# preamp.net
KiCad netlist of a schematic drawn in Altium Designer
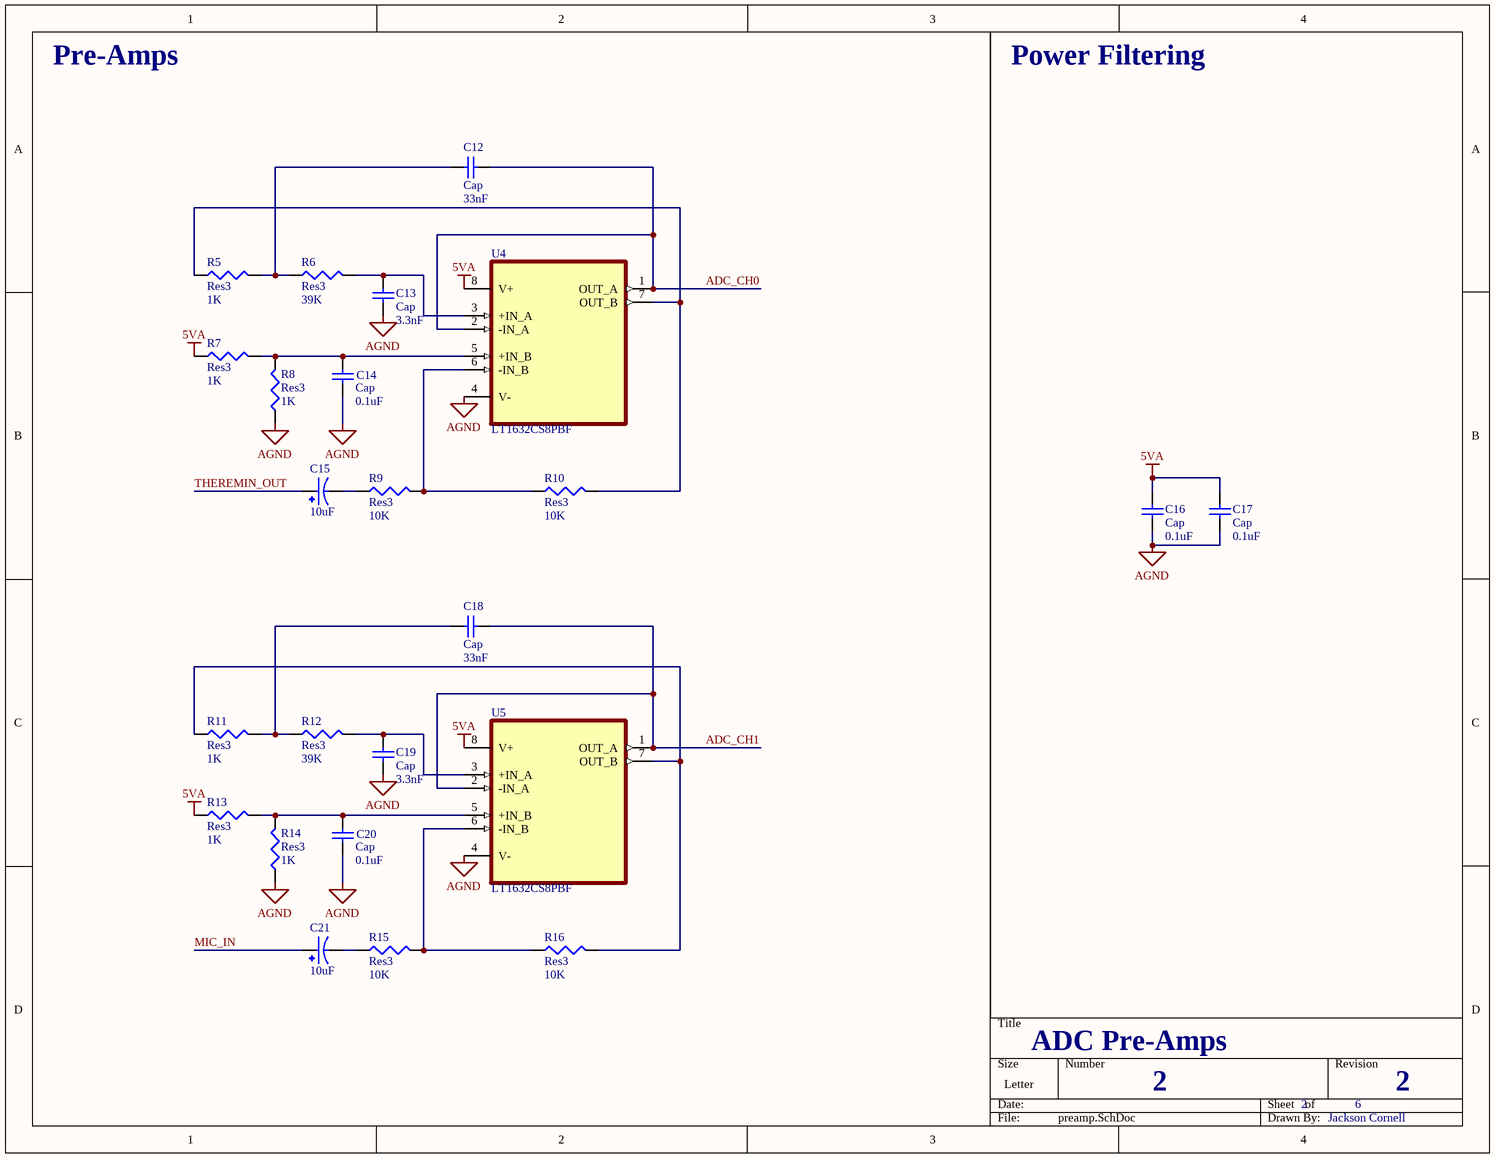
[diagram p0: preamp.SchDoc]

(export (version "E")
  (design (tool "Eeschema 10.0.6"))
  (components
    (comp (ref "C12")
      (value "Cap")
      (footprint "CAPC0805")
      (description "Capacitor")
      (fields (field (name "ALTIUM_VALUE") "33nF") (field (name "PUBLISHER") "Altium Limited"))
      (libsource (lib "Miscellaneous Devices") (part "Cap"))
    )
    (comp (ref "C13")
      (value "Cap")
      (footprint "CAPC0805")
      (description "Capacitor")
      (fields (field (name "ALTIUM_VALUE") "3.3nF") (field (name "PUBLISHER") "Altium Limited"))
      (libsource (lib "Miscellaneous Devices") (part "Cap"))
    )
    (comp (ref "C14")
      (value "Cap")
      (footprint "CAPC0805")
      (description "Capacitor")
      (fields (field (name "ALTIUM_VALUE") "0.1uF") (field (name "PUBLISHER") "Altium Limited"))
      (libsource (lib "Miscellaneous Devices") (part "Cap"))
    )
    (comp (ref "C15")
      (value "10uF")
      (footprint "CAPPRD200W50D500H1250")
      (description "Aluminum Electrolytic Capacitors, 220uF, 6.3V, -40 to 105C")
      (fields (field (name "MF") "Panasonic") (field (name "MP") "EEUFS0J221B"))
      (libsource (lib "EEUFS0J221B") (part "EEUFS0J221B"))
    )
    (comp (ref "C16")
      (value "Cap")
      (footprint "CAPC0805")
      (description "Capacitor")
      (fields (field (name "ALTIUM_VALUE") "0.1uF") (field (name "PUBLISHER") "Altium Limited"))
      (libsource (lib "Miscellaneous Devices") (part "Cap"))
    )
    (comp (ref "C17")
      (value "Cap")
      (footprint "CAPC0805")
      (description "Capacitor")
      (fields (field (name "ALTIUM_VALUE") "0.1uF") (field (name "PUBLISHER") "Altium Limited"))
      (libsource (lib "Miscellaneous Devices") (part "Cap"))
    )
    (comp (ref "C18")
      (value "Cap")
      (footprint "CAPC0805")
      (description "Capacitor")
      (fields (field (name "ALTIUM_VALUE") "33nF") (field (name "PUBLISHER") "Altium Limited"))
      (libsource (lib "Miscellaneous Devices") (part "Cap"))
    )
    (comp (ref "C19")
      (value "Cap")
      (footprint "CAPC0805")
      (description "Capacitor")
      (fields (field (name "ALTIUM_VALUE") "3.3nF") (field (name "PUBLISHER") "Altium Limited"))
      (libsource (lib "Miscellaneous Devices") (part "Cap"))
    )
    (comp (ref "C20")
      (value "Cap")
      (footprint "CAPC0805")
      (description "Capacitor")
      (fields (field (name "ALTIUM_VALUE") "0.1uF") (field (name "PUBLISHER") "Altium Limited"))
      (libsource (lib "Miscellaneous Devices") (part "Cap"))
    )
    (comp (ref "C21")
      (value "10uF")
      (footprint "CAPPRD200W50D500H1250")
      (description "Aluminum Electrolytic Capacitors, 220uF, 6.3V, -40 to 105C")
      (fields (field (name "MF") "Panasonic") (field (name "MP") "EEUFS0J221B"))
      (libsource (lib "EEUFS0J221B") (part "EEUFS0J221B"))
    )
    (comp (ref "R5")
      (value "Res3")
      (footprint "RES0805")
      (description "Resistor")
      (fields (field (name "ALTIUM_VALUE") "1K") (field (name "PUBLISHER") "Altium Limited"))
      (libsource (lib "Miscellaneous Devices") (part "Res3"))
    )
    (comp (ref "R6")
      (value "Res3")
      (footprint "RES0805")
      (description "Resistor")
      (fields (field (name "ALTIUM_VALUE") "39K") (field (name "PUBLISHER") "Altium Limited"))
      (libsource (lib "Miscellaneous Devices") (part "Res3"))
    )
    (comp (ref "R7")
      (value "Res3")
      (footprint "RES0805")
      (description "Resistor")
      (fields (field (name "ALTIUM_VALUE") "1K") (field (name "PUBLISHER") "Altium Limited"))
      (libsource (lib "Miscellaneous Devices") (part "Res3"))
    )
    (comp (ref "R8")
      (value "Res3")
      (footprint "RES0805")
      (description "Resistor")
      (fields (field (name "ALTIUM_VALUE") "1K") (field (name "PUBLISHER") "Altium Limited"))
      (libsource (lib "Miscellaneous Devices") (part "Res3"))
    )
    (comp (ref "R9")
      (value "Res3")
      (footprint "RES0805")
      (description "Resistor")
      (fields (field (name "ALTIUM_VALUE") "10K") (field (name "PUBLISHER") "Altium Limited"))
      (libsource (lib "Miscellaneous Devices") (part "Res3"))
    )
    (comp (ref "R10")
      (value "Res3")
      (footprint "RES0805")
      (description "Resistor")
      (fields (field (name "ALTIUM_VALUE") "10K") (field (name "PUBLISHER") "Altium Limited"))
      (libsource (lib "Miscellaneous Devices") (part "Res3"))
    )
    (comp (ref "R11")
      (value "Res3")
      (footprint "RES0805")
      (description "Resistor")
      (fields (field (name "ALTIUM_VALUE") "1K") (field (name "PUBLISHER") "Altium Limited"))
      (libsource (lib "Miscellaneous Devices") (part "Res3"))
    )
    (comp (ref "R12")
      (value "Res3")
      (footprint "RES0805")
      (description "Resistor")
      (fields (field (name "ALTIUM_VALUE") "39K") (field (name "PUBLISHER") "Altium Limited"))
      (libsource (lib "Miscellaneous Devices") (part "Res3"))
    )
    (comp (ref "R13")
      (value "Res3")
      (footprint "RES0805")
      (description "Resistor")
      (fields (field (name "ALTIUM_VALUE") "1K") (field (name "PUBLISHER") "Altium Limited"))
      (libsource (lib "Miscellaneous Devices") (part "Res3"))
    )
    (comp (ref "R14")
      (value "Res3")
      (footprint "RES0805")
      (description "Resistor")
      (fields (field (name "ALTIUM_VALUE") "1K") (field (name "PUBLISHER") "Altium Limited"))
      (libsource (lib "Miscellaneous Devices") (part "Res3"))
    )
    (comp (ref "R15")
      (value "Res3")
      (footprint "RES0805")
      (description "Resistor")
      (fields (field (name "ALTIUM_VALUE") "10K") (field (name "PUBLISHER") "Altium Limited"))
      (libsource (lib "Miscellaneous Devices") (part "Res3"))
    )
    (comp (ref "R16")
      (value "Res3")
      (footprint "RES0805")
      (description "Resistor")
      (fields (field (name "ALTIUM_VALUE") "10K") (field (name "PUBLISHER") "Altium Limited"))
      (libsource (lib "Miscellaneous Devices") (part "Res3"))
    )
    (comp (ref "U4")
      (value "LT1632CS8PBF")
      (footprint "SO-8_S")
      (description "45MHz, 45V/ms, Dual/Quad Rail-to-Rail Input and Output  Precision Op Amps")
      (libsource (lib "LT1632CS8PBF") (part "LT1632CS8PBF"))
    )
    (comp (ref "U5")
      (value "LT1632CS8PBF")
      (footprint "SO-8_S")
      (description "45MHz, 45V/ms, Dual/Quad Rail-to-Rail Input and Output  Precision Op Amps")
      (libsource (lib "LT1632CS8PBF") (part "LT1632CS8PBF"))
    )
  )
  (nets
    (net (code "1") (name "/ADC_CH0") (class "Default")
      (node (ref "C12") (pin "2") (pinfunction "2_2") (pintype "passive"))
      (node (ref "U4") (pin "1") (pinfunction "OUT_A_1") (pintype "output"))
      (node (ref "U4") (pin "2") (pinfunction "-IN_A_2") (pintype "input"))
    )
    (net (code "2") (name "/ADC_CH1") (class "Default")
      (node (ref "C18") (pin "2") (pinfunction "2_2") (pintype "passive"))
      (node (ref "U5") (pin "1") (pinfunction "OUT_A_1") (pintype "output"))
      (node (ref "U5") (pin "2") (pinfunction "-IN_A_2") (pintype "input"))
    )
    (net (code "3") (name "/MIC_IN") (class "Default")
      (node (ref "C21") (pin "P") (pinfunction "P_P") (pintype "passive"))
    )
    (net (code "4") (name "/THEREMIN_OUT") (class "Default")
      (node (ref "C15") (pin "P") (pinfunction "P_P") (pintype "passive"))
    )
    (net (code "5") (name "5VA") (class "Default")
      (node (ref "C16") (pin "2") (pinfunction "2_2") (pintype "passive"))
      (node (ref "C17") (pin "2") (pinfunction "2_2") (pintype "passive"))
      (node (ref "R13") (pin "1") (pinfunction "1_1") (pintype "passive"))
      (node (ref "R7") (pin "1") (pinfunction "1_1") (pintype "passive"))
      (node (ref "U4") (pin "8") (pinfunction "V+_8") (pintype "power_in"))
      (node (ref "U5") (pin "8") (pinfunction "V+_8") (pintype "power_in"))
    )
    (net (code "6") (name "AGND") (class "Default")
      (node (ref "C13") (pin "1") (pinfunction "1_1") (pintype "passive"))
      (node (ref "C14") (pin "1") (pinfunction "1_1") (pintype "passive"))
      (node (ref "C16") (pin "1") (pinfunction "1_1") (pintype "passive"))
      (node (ref "C17") (pin "1") (pinfunction "1_1") (pintype "passive"))
      (node (ref "C19") (pin "1") (pinfunction "1_1") (pintype "passive"))
      (node (ref "C20") (pin "1") (pinfunction "1_1") (pintype "passive"))
      (node (ref "R14") (pin "1") (pinfunction "1_1") (pintype "passive"))
      (node (ref "R8") (pin "1") (pinfunction "1_1") (pintype "passive"))
      (node (ref "U4") (pin "4") (pinfunction "V-_4") (pintype "power_in"))
      (node (ref "U5") (pin "4") (pinfunction "V-_4") (pintype "power_in"))
    )
    (net (code "7") (name "Net-(C12-Pad1)") (class "Default")
      (node (ref "C12") (pin "1") (pinfunction "1_1") (pintype "passive"))
      (node (ref "R5") (pin "2") (pinfunction "2_2") (pintype "passive"))
      (node (ref "R6") (pin "1") (pinfunction "1_1") (pintype "passive"))
    )
    (net (code "8") (name "Net-(C15-PadN)") (class "Default")
      (node (ref "C15") (pin "N") (pinfunction "N_N") (pintype "passive"))
      (node (ref "R9") (pin "1") (pinfunction "1_1") (pintype "passive"))
    )
    (net (code "9") (name "Net-(C18-Pad1)") (class "Default")
      (node (ref "C18") (pin "1") (pinfunction "1_1") (pintype "passive"))
      (node (ref "R11") (pin "2") (pinfunction "2_2") (pintype "passive"))
      (node (ref "R12") (pin "1") (pinfunction "1_1") (pintype "passive"))
    )
    (net (code "10") (name "Net-(C21-PadN)") (class "Default")
      (node (ref "C21") (pin "N") (pinfunction "N_N") (pintype "passive"))
      (node (ref "R15") (pin "1") (pinfunction "1_1") (pintype "passive"))
    )
    (net (code "11") (name "Net-(U4-+IN_A)") (class "Default")
      (node (ref "C13") (pin "2") (pinfunction "2_2") (pintype "passive"))
      (node (ref "R6") (pin "2") (pinfunction "2_2") (pintype "passive"))
      (node (ref "U4") (pin "3") (pinfunction "+IN_A_3") (pintype "input"))
    )
    (net (code "12") (name "Net-(U4-+IN_B)") (class "Default")
      (node (ref "C14") (pin "2") (pinfunction "2_2") (pintype "passive"))
      (node (ref "R7") (pin "2") (pinfunction "2_2") (pintype "passive"))
      (node (ref "R8") (pin "2") (pinfunction "2_2") (pintype "passive"))
      (node (ref "U4") (pin "5") (pinfunction "+IN_B_5") (pintype "input"))
    )
    (net (code "13") (name "Net-(U4--IN_B)") (class "Default")
      (node (ref "R10") (pin "1") (pinfunction "1_1") (pintype "passive"))
      (node (ref "R9") (pin "2") (pinfunction "2_2") (pintype "passive"))
      (node (ref "U4") (pin "6") (pinfunction "-IN_B_6") (pintype "input"))
    )
    (net (code "14") (name "Net-(U4-OUT_B)") (class "Default")
      (node (ref "R10") (pin "2") (pinfunction "2_2") (pintype "passive"))
      (node (ref "R5") (pin "1") (pinfunction "1_1") (pintype "passive"))
      (node (ref "U4") (pin "7") (pinfunction "OUT_B_7") (pintype "output"))
    )
    (net (code "15") (name "Net-(U5-+IN_A)") (class "Default")
      (node (ref "C19") (pin "2") (pinfunction "2_2") (pintype "passive"))
      (node (ref "R12") (pin "2") (pinfunction "2_2") (pintype "passive"))
      (node (ref "U5") (pin "3") (pinfunction "+IN_A_3") (pintype "input"))
    )
    (net (code "16") (name "Net-(U5-+IN_B)") (class "Default")
      (node (ref "C20") (pin "2") (pinfunction "2_2") (pintype "passive"))
      (node (ref "R13") (pin "2") (pinfunction "2_2") (pintype "passive"))
      (node (ref "R14") (pin "2") (pinfunction "2_2") (pintype "passive"))
      (node (ref "U5") (pin "5") (pinfunction "+IN_B_5") (pintype "input"))
    )
    (net (code "17") (name "Net-(U5--IN_B)") (class "Default")
      (node (ref "R15") (pin "2") (pinfunction "2_2") (pintype "passive"))
      (node (ref "R16") (pin "1") (pinfunction "1_1") (pintype "passive"))
      (node (ref "U5") (pin "6") (pinfunction "-IN_B_6") (pintype "input"))
    )
    (net (code "18") (name "Net-(U5-OUT_B)") (class "Default")
      (node (ref "R11") (pin "1") (pinfunction "1_1") (pintype "passive"))
      (node (ref "R16") (pin "2") (pinfunction "2_2") (pintype "passive"))
      (node (ref "U5") (pin "7") (pinfunction "OUT_B_7") (pintype "output"))
    )
  )
)
